# Sheet2.net
KiCad netlist of a schematic drawn in Altium Designer
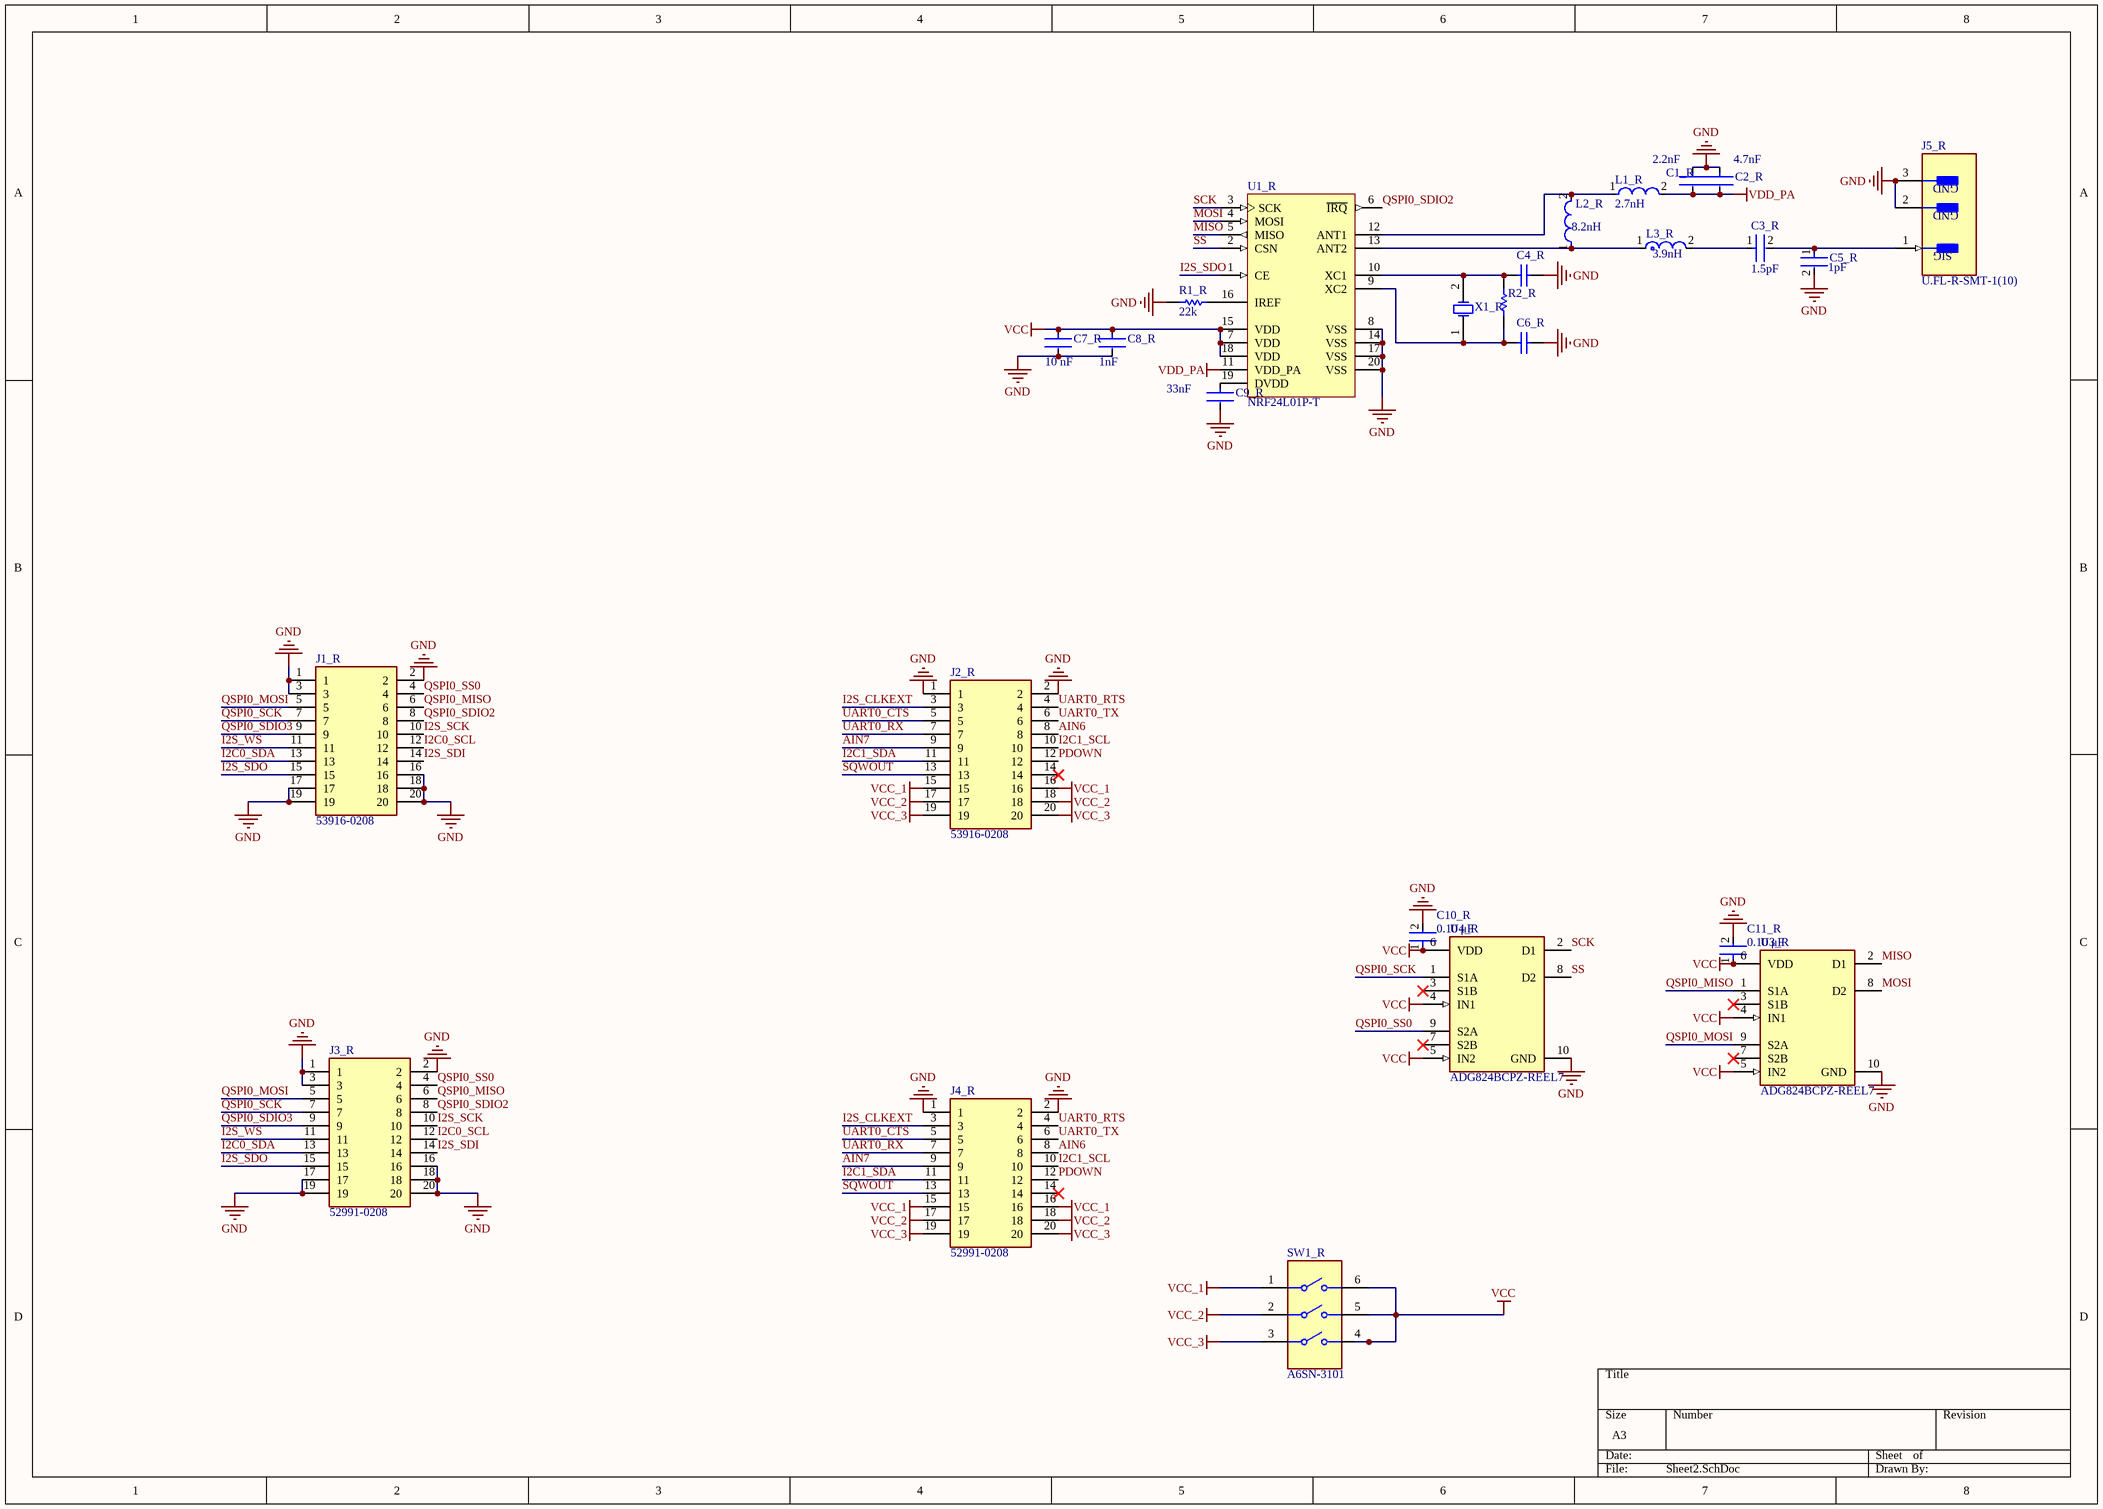
[diagram p0: Sheet2.SchDoc]

(export (version "E")
  (design (tool "Eeschema 10.0.6"))
  (components
    (comp (ref "C1_R")
      (value "GRM155R71H222KA01D")
      (footprint "FP-GRM155-0_05-IPC_B")
      (description "Chip Multilayer Ceramic Capacitors for General Purpose, 0402, 2200pF, X7R, 15%, 10%, 50V")
      (fields
        (field (name "VOLTAGE") "50V")
        (field (name "TOLERANCE") "10%")
        (field (name "CAPACITANCE") "2.2nF")
      )
      (libsource (lib "Altium Content Vault") (part "02cd4be3c70576c341d710602a673aa"))
    )
    (comp (ref "C2_R")
      (value "GRM155R71H472KA01D")
      (footprint "FP-GRM155-0_05-IPC_B")
      (description "Chip Multilayer Ceramic Capacitors for General Purpose, 0402, 4700pF, X7R, 15%, 10%, 50V")
      (fields
        (field (name "VOLTAGE") "50V")
        (field (name "CAPACITANCE") "4.7nF")
        (field (name "TOLERANCE") "10%")
      )
      (libsource (lib "Altium Content Vault") (part "02cd4be3c70576c341d710602a673aa"))
    )
    (comp (ref "C3_R")
      (value "GJM1555C1H1R5BB01D")
      (footprint "FP-GJM155-0_05-IPC_C")
      (description "Multi-Layer Ceramic Capacitor 1.5pF C0G  ±0.1pF 0402 Paper T/R")
      (fields (field (name "CAPACITANCE") "1.5pF") (field (name "VOLTAGE") "50V"))
      (libsource (lib "") (part "02cd4be3c70576c341d710602a673aa_1"))
    )
    (comp (ref "C4_R")
      (value "04025A220JAT2A")
      (footprint "CAPC1005X56X25NL10T15")
      (fields (field (name "MANUFACTURER") "AVX Interconnect / Elco"))
      (libsource (lib "Altium Content Vault") (part "CAP"))
    )
    (comp (ref "C5_R")
      (value "GJM1555C1H1R0BB01D")
      (footprint "FP-GJM155-0_05-IPC_B")
      (description "Multi-Layer Ceramic Capacitor 1pF C0G  ±0.1pF 0402 Paper T/R")
      (fields (field (name "CAPACITANCE") "1pF") (field (name "VOLTAGE") "50V"))
      (libsource (lib "") (part "02cd4be3c70576c341d710602a673aa_1"))
    )
    (comp (ref "C6_R")
      (value "04025A220JAT2A")
      (footprint "CAPC1005X56X25NL10T15")
      (fields (field (name "MANUFACTURER") "AVX Interconnect / Elco"))
      (libsource (lib "Altium Content Vault") (part "CAP"))
    )
    (comp (ref "C7_R")
      (value "CC0402KRX7R7BB103")
      (footprint "FP-CC0402-MFG")
      (description "CAP CER 10000PF 16V X7R 0402")
      (fields
        (field (name "CAPACITANCE") "10 nF")
        (field (name "TOLERANCE") "0.1")
        (field (name "MANUFACTURER") "YAGEO")
      )
      (libsource (lib "Altium Content Vault") (part "11868f565c42a9108669ba33697ecf6"))
    )
    (comp (ref "C8_R")
      (value "GRM1555C1H102JA01D")
      (footprint "FP-GRM155-0_05-IPC_B")
      (description "Chip Multilayer Ceramic Capacitors for General Purpose, 0402, 1000pF, C0G, 30ppm/°C, 5%, 50V")
      (fields
        (field (name "TOLERANCE") "5%")
        (field (name "VOLTAGE") "50V")
        (field (name "CAPACITANCE") "1nF")
      )
      (libsource (lib "Altium Content Vault") (part "02cd4be3c70576c341d710602a673aa"))
    )
    (comp (ref "C9_R")
      (value "C0402C333K4RACTU")
      (footprint "FP-C0402-BB-MFG")
      (description "0402 C 33nF Ceramic Multilayer Capacitor; 16 V; +125degC; X7R Dielectric; +/-10%")
      (fields
        (field (name "MANUFACTURER") "Kemet")
        (field (name "CAPACITANCE") "33nF")
        (field (name "OCTOPART") "https://octopart.com/c0402c333k4ractu-kemet-128815")
      )
      (libsource (lib "") (part "b4654b650e69147ec39a6b967a45e02_1"))
    )
    (comp (ref "C10_R")
      (value "C0402C104K8PACTU")
      (footprint "FP-C0402-BB-MFG")
      (description "CAP CER 0.1UF 10V X5R 0402")
      (fields
        (field (name "CAPACITANCE") "0.10 μF")
        (field (name "MANUFACTURER") "Kemet")
        (field (name "TOLERANCE") "0.1")
      )
      (libsource (lib "Altium Content Vault") (part "b4654b650e69147ec39a6b967a45e02"))
    )
    (comp (ref "C11_R")
      (value "C0402C104K8PACTU")
      (footprint "FP-C0402-BB-MFG")
      (description "CAP CER 0.1UF 10V X5R 0402")
      (fields
        (field (name "CAPACITANCE") "0.10 μF")
        (field (name "MANUFACTURER") "Kemet")
        (field (name "TOLERANCE") "0.1")
      )
      (libsource (lib "Altium Content Vault") (part "b4654b650e69147ec39a6b967a45e02"))
    )
    (comp (ref "J1_R")
      (value "53916-0208")
      (footprint "MOLEX-  539160208")
      (libsource (lib "52991-0208") (part "53916-0208"))
    )
    (comp (ref "J2_R")
      (value "53916-0208")
      (footprint "MOLEX-  539160208")
      (libsource (lib "52991-0208") (part "53916-0208"))
    )
    (comp (ref "J3_R")
      (value "52991-0208")
      (footprint "MOLEX_52991-0208")
      (description "20 Position Connector Receptacle, Center Strip Contacts Surface Mount Gold")
      (fields (field (name "MF") "Molex"))
      (libsource (lib "52991-0208") (part "52991-0208"))
    )
    (comp (ref "J4_R")
      (value "52991-0208")
      (footprint "MOLEX_52991-0208")
      (description "20 Position Connector Receptacle, Center Strip Contacts Surface Mount Gold")
      (fields (field (name "MF") "Molex"))
      (libsource (lib "52991-0208") (part "52991-0208"))
    )
    (comp (ref "J5_R")
      (value "U.FL-R-SMT-1(10)")
      (footprint "FP-U_FL-R-SMT-1_10-MFG")
      (description "CONN U.FL RCPT STR 50 OHM SMD")
      (libsource (lib "Altium Content Vault") (part "7158abf7d987fa84906f6fb0d115710"))
    )
    (comp (ref "L1_R")
      (value "LQW15AN2N7C00D")
      (footprint "FP-LQW15AN_00-W0_6-0_1-MFG")
      (description "Wire Wound RF Inductor 2.7nH ±0.2nH 850mA 0.05Ω 0402 (1005)")
      (fields (field (name "INDUCTANCE") "2.7nH"))
      (libsource (lib "Altium Content Vault") (part "725321dda6339637d4d059423bc1c3c"))
    )
    (comp (ref "L2_R")
      (value "LQW15AN8N2G00D")
      (footprint "FP-LQW15AN_00-W0_6-0_1-MFG")
      (description "Wire Wound RF Inductor 8.2nH ±2% 540mA 0.14Ω 0402 (1005)")
      (fields (field (name "TOLERANCE") "2%") (field (name "INDUCTANCE") "8.2nH"))
      (libsource (lib "Altium Content Vault") (part "725321dda6339637d4d059423bc1c3c"))
    )
    (comp (ref "L3_R")
      (value "LQG15HN3N9S02D")
      (footprint "FP-LQG15HH_02-MFG")
      (description "Multilayer type RF Inductor 3.9nH ±0.3nH 0.13Ω 700mA 0402")
      (fields (field (name "INDUCTANCE") "3.9nH"))
      (libsource (lib "Altium Content Vault") (part "4cc4b267dca4c8e51f7102f422741d8"))
    )
    (comp (ref "R1_R")
      (value "CRCW040222K0FKED")
      (footprint "RESC1005X40X25NL05T05")
      (fields (field (name "MANUFACTURER") "Vishay Dale") (field (name "RESISTANCE") "22k"))
      (libsource (lib "Altium Content Vault") (part "RES"))
    )
    (comp (ref "R2_R")
      (value "ERJ-3EKF1004V")
      (footprint "RESC1608X55X30LL15T15")
      (fields (field (name "MANUFACTURER") "Panasonic"))
      (libsource (lib "Altium Content Vault") (part "RES"))
    )
    (comp (ref "SW1_R")
      (value "A6SN-3101")
      (footprint "FP-A6SN-3101-MFG")
      (description "DIP Switches / SIP Switches 3P Knife-Edge, 2.3mm Slide SMT Flat-Act")
      (fields (field (name "MANUFACTURER") "Omron Electronics Inc-EMC Div"))
      (libsource (lib "Altium Content Vault") (part "c5ed29025a0a80be921a75429a93ff4"))
    )
    (comp (ref "U1_R")
      (value "NRF24L01P-T")
      (footprint "NRSC-QFN-20_L")
      (description "Single Chip Transceiver, 2.4 GHz, 60 mW, 1.9 to 3.6 V, -40 to 85 degC, 20-Pin QFN, RoHS, Tray")
      (fields (field (name "MANUFACTURER") "Nordic Semiconductor"))
      (libsource (lib "Altium Content Vault") (part "NRSC-NRF24L01P-QFN-20"))
    )
    (comp (ref "U3_R")
      (value "ADG824BCPZ-REEL7")
      (footprint "FP-CP-10-10-MFG")
      (description "IC SWITCH DUAL SPDT 10LFCSP")
      (fields
        (field (name "OCTOPART") "https://octopart.com/adg824bcpz-reel7-analog+devices-12410880")
        (field (name "MANUFACTURER") "Analog Devices")
      )
      (libsource (lib "Altium Content Vault") (part "750f7653eda72c1ba3820f182f788e1"))
    )
    (comp (ref "U4_R")
      (value "ADG824BCPZ-REEL7")
      (footprint "FP-CP-10-10-MFG")
      (description "IC SWITCH DUAL SPDT 10LFCSP")
      (fields
        (field (name "OCTOPART") "https://octopart.com/adg824bcpz-reel7-analog+devices-12410880")
        (field (name "MANUFACTURER") "Analog Devices")
      )
      (libsource (lib "Altium Content Vault") (part "750f7653eda72c1ba3820f182f788e1"))
    )
    (comp (ref "X1_R")
      (value "FOXSDLF/160-20")
      (footprint "FOX-FOXSDLF160-20_V")
      (libsource (lib "Altium Content Vault") (part "XTAL_1-2-2"))
    )
  )
  (nets
    (net (code "1") (name "/AIN6") (class "Default")
      (node (ref "J2_R") (pin "8") (pinfunction "8_8") (pintype "passive"))
      (node (ref "J4_R") (pin "8") (pinfunction "8_8") (pintype "passive"))
    )
    (net (code "2") (name "/AIN7") (class "Default")
      (node (ref "J2_R") (pin "9") (pinfunction "9_9") (pintype "passive"))
      (node (ref "J4_R") (pin "9") (pinfunction "9_9") (pintype "passive"))
    )
    (net (code "3") (name "/I2C0_SCL") (class "Default")
      (node (ref "J1_R") (pin "12") (pinfunction "12_12") (pintype "passive"))
      (node (ref "J3_R") (pin "12") (pinfunction "12_12") (pintype "passive"))
    )
    (net (code "4") (name "/I2C0_SDA") (class "Default")
      (node (ref "J1_R") (pin "13") (pinfunction "13_13") (pintype "passive"))
      (node (ref "J3_R") (pin "13") (pinfunction "13_13") (pintype "passive"))
    )
    (net (code "5") (name "/I2C1_SCL") (class "Default")
      (node (ref "J2_R") (pin "10") (pinfunction "10_10") (pintype "passive"))
      (node (ref "J4_R") (pin "10") (pinfunction "10_10") (pintype "passive"))
    )
    (net (code "6") (name "/I2C1_SDA") (class "Default")
      (node (ref "J2_R") (pin "11") (pinfunction "11_11") (pintype "passive"))
      (node (ref "J4_R") (pin "11") (pinfunction "11_11") (pintype "passive"))
    )
    (net (code "7") (name "/I2S_CLKEXT") (class "Default")
      (node (ref "J2_R") (pin "3") (pinfunction "3_3") (pintype "passive"))
      (node (ref "J4_R") (pin "3") (pinfunction "3_3") (pintype "passive"))
    )
    (net (code "8") (name "/I2S_SCK") (class "Default")
      (node (ref "J1_R") (pin "10") (pinfunction "10_10") (pintype "passive"))
      (node (ref "J3_R") (pin "10") (pinfunction "10_10") (pintype "passive"))
    )
    (net (code "9") (name "/I2S_SDI") (class "Default")
      (node (ref "J1_R") (pin "14") (pinfunction "14_14") (pintype "passive"))
      (node (ref "J3_R") (pin "14") (pinfunction "14_14") (pintype "passive"))
    )
    (net (code "10") (name "/I2S_SDO") (class "Default")
      (node (ref "J1_R") (pin "15") (pinfunction "15_15") (pintype "passive"))
      (node (ref "J3_R") (pin "15") (pinfunction "15_15") (pintype "passive"))
      (node (ref "U1_R") (pin "1") (pinfunction "CE_1") (pintype "input"))
    )
    (net (code "11") (name "/I2S_WS") (class "Default")
      (node (ref "J1_R") (pin "11") (pinfunction "11_11") (pintype "passive"))
      (node (ref "J3_R") (pin "11") (pinfunction "11_11") (pintype "passive"))
    )
    (net (code "12") (name "/MISO") (class "Default")
      (node (ref "U1_R") (pin "5") (pinfunction "MISO_5") (pintype "output"))
      (node (ref "U3_R") (pin "2") (pinfunction "D1_2") (pintype "passive"))
    )
    (net (code "13") (name "/MOSI") (class "Default")
      (node (ref "U1_R") (pin "4") (pinfunction "MOSI_4") (pintype "input"))
      (node (ref "U3_R") (pin "8") (pinfunction "D2_8") (pintype "passive"))
    )
    (net (code "14") (name "/PDOWN") (class "Default")
      (node (ref "J2_R") (pin "12") (pinfunction "12_12") (pintype "passive"))
      (node (ref "J4_R") (pin "12") (pinfunction "12_12") (pintype "passive"))
    )
    (net (code "15") (name "/QSPI0_MISO") (class "Default")
      (node (ref "J1_R") (pin "6") (pinfunction "6_6") (pintype "passive"))
      (node (ref "J3_R") (pin "6") (pinfunction "6_6") (pintype "passive"))
      (node (ref "U3_R") (pin "1") (pinfunction "S1A_1") (pintype "passive"))
    )
    (net (code "16") (name "/QSPI0_MOSI") (class "Default")
      (node (ref "J1_R") (pin "5") (pinfunction "5_5") (pintype "passive"))
      (node (ref "J3_R") (pin "5") (pinfunction "5_5") (pintype "passive"))
      (node (ref "U3_R") (pin "9") (pinfunction "S2A_9") (pintype "passive"))
    )
    (net (code "17") (name "/QSPI0_SCK") (class "Default")
      (node (ref "J1_R") (pin "7") (pinfunction "7_7") (pintype "passive"))
      (node (ref "J3_R") (pin "7") (pinfunction "7_7") (pintype "passive"))
      (node (ref "U4_R") (pin "1") (pinfunction "S1A_1") (pintype "passive"))
    )
    (net (code "18") (name "/QSPI0_SDIO2") (class "Default")
      (node (ref "J1_R") (pin "8") (pinfunction "8_8") (pintype "passive"))
      (node (ref "J3_R") (pin "8") (pinfunction "8_8") (pintype "passive"))
      (node (ref "U1_R") (pin "6") (pinfunction "~{IRQ}_6") (pintype "output"))
    )
    (net (code "19") (name "/QSPI0_SDIO3") (class "Default")
      (node (ref "J1_R") (pin "9") (pinfunction "9_9") (pintype "passive"))
      (node (ref "J3_R") (pin "9") (pinfunction "9_9") (pintype "passive"))
    )
    (net (code "20") (name "/QSPI0_SS0") (class "Default")
      (node (ref "J1_R") (pin "4") (pinfunction "4_4") (pintype "passive"))
      (node (ref "J3_R") (pin "4") (pinfunction "4_4") (pintype "passive"))
      (node (ref "U4_R") (pin "9") (pinfunction "S2A_9") (pintype "passive"))
    )
    (net (code "21") (name "/SCK") (class "Default")
      (node (ref "U1_R") (pin "3") (pinfunction "SCK_3") (pintype "input"))
      (node (ref "U4_R") (pin "2") (pinfunction "D1_2") (pintype "passive"))
    )
    (net (code "22") (name "/SQWOUT") (class "Default")
      (node (ref "J2_R") (pin "13") (pinfunction "13_13") (pintype "passive"))
      (node (ref "J4_R") (pin "13") (pinfunction "13_13") (pintype "passive"))
    )
    (net (code "23") (name "/SS") (class "Default")
      (node (ref "U1_R") (pin "2") (pinfunction "CSN_2") (pintype "input"))
      (node (ref "U4_R") (pin "8") (pinfunction "D2_8") (pintype "passive"))
    )
    (net (code "24") (name "/UART0_CTS") (class "Default")
      (node (ref "J2_R") (pin "5") (pinfunction "5_5") (pintype "passive"))
      (node (ref "J4_R") (pin "5") (pinfunction "5_5") (pintype "passive"))
    )
    (net (code "25") (name "/UART0_RTS") (class "Default")
      (node (ref "J2_R") (pin "4") (pinfunction "4_4") (pintype "passive"))
      (node (ref "J4_R") (pin "4") (pinfunction "4_4") (pintype "passive"))
    )
    (net (code "26") (name "/UART0_RX") (class "Default")
      (node (ref "J2_R") (pin "7") (pinfunction "7_7") (pintype "passive"))
      (node (ref "J4_R") (pin "7") (pinfunction "7_7") (pintype "passive"))
    )
    (net (code "27") (name "/UART0_TX") (class "Default")
      (node (ref "J2_R") (pin "6") (pinfunction "6_6") (pintype "passive"))
      (node (ref "J4_R") (pin "6") (pinfunction "6_6") (pintype "passive"))
    )
    (net (code "28") (name "GND") (class "Default")
      (node (ref "C10_R") (pin "2") (pinfunction "2_2") (pintype "passive"))
      (node (ref "C11_R") (pin "2") (pinfunction "2_2") (pintype "passive"))
      (node (ref "C1_R") (pin "1") (pinfunction "1_1") (pintype "passive"))
      (node (ref "C2_R") (pin "1") (pinfunction "1_1") (pintype "passive"))
      (node (ref "C4_R") (pin "2") (pinfunction "2_2") (pintype "passive"))
      (node (ref "C5_R") (pin "2") (pinfunction "2_2") (pintype "passive"))
      (node (ref "C6_R") (pin "2") (pinfunction "2_2") (pintype "passive"))
      (node (ref "C7_R") (pin "2") (pinfunction "2_2") (pintype "passive"))
      (node (ref "C8_R") (pin "2") (pinfunction "2_2") (pintype "passive"))
      (node (ref "C9_R") (pin "2") (pinfunction "2_2") (pintype "passive"))
      (node (ref "J1_R") (pin "1") (pinfunction "1_1") (pintype "passive"))
      (node (ref "J1_R") (pin "16") (pinfunction "16_16") (pintype "passive"))
      (node (ref "J1_R") (pin "17") (pinfunction "17_17") (pintype "passive"))
      (node (ref "J1_R") (pin "18") (pinfunction "18_18") (pintype "passive"))
      (node (ref "J1_R") (pin "19") (pinfunction "19_19") (pintype "passive"))
      (node (ref "J1_R") (pin "2") (pinfunction "2_2") (pintype "passive"))
      (node (ref "J1_R") (pin "20") (pinfunction "20_20") (pintype "passive"))
      (node (ref "J1_R") (pin "3") (pinfunction "3_3") (pintype "passive"))
      (node (ref "J2_R") (pin "1") (pinfunction "1_1") (pintype "passive"))
      (node (ref "J2_R") (pin "2") (pinfunction "2_2") (pintype "passive"))
      (node (ref "J3_R") (pin "1") (pinfunction "1_1") (pintype "passive"))
      (node (ref "J3_R") (pin "16") (pinfunction "16_16") (pintype "passive"))
      (node (ref "J3_R") (pin "17") (pinfunction "17_17") (pintype "passive"))
      (node (ref "J3_R") (pin "18") (pinfunction "18_18") (pintype "passive"))
      (node (ref "J3_R") (pin "19") (pinfunction "19_19") (pintype "passive"))
      (node (ref "J3_R") (pin "2") (pinfunction "2_2") (pintype "passive"))
      (node (ref "J3_R") (pin "20") (pinfunction "20_20") (pintype "passive"))
      (node (ref "J3_R") (pin "3") (pinfunction "3_3") (pintype "passive"))
      (node (ref "J4_R") (pin "1") (pinfunction "1_1") (pintype "passive"))
      (node (ref "J4_R") (pin "2") (pinfunction "2_2") (pintype "passive"))
      (node (ref "J5_R") (pin "2") (pinfunction "GND_2") (pintype "power_in"))
      (node (ref "J5_R") (pin "3") (pinfunction "GND_3") (pintype "power_in"))
      (node (ref "R1_R") (pin "1") (pinfunction "1_1") (pintype "passive"))
      (node (ref "U1_R") (pin "14") (pinfunction "VSS_14") (pintype "power_in"))
      (node (ref "U1_R") (pin "17") (pinfunction "VSS_17") (pintype "power_in"))
      (node (ref "U1_R") (pin "20") (pinfunction "VSS_20") (pintype "power_in"))
      (node (ref "U1_R") (pin "8") (pinfunction "VSS_8") (pintype "power_in"))
      (node (ref "U3_R") (pin "10") (pinfunction "GND_10") (pintype "power_in"))
      (node (ref "U4_R") (pin "10") (pinfunction "GND_10") (pintype "power_in"))
    )
    (net (code "29") (name "Net-(C3_R-Pad1)") (class "Default")
      (node (ref "C3_R") (pin "1") (pinfunction "1_1") (pintype "passive"))
      (node (ref "L3_R") (pin "2") (pinfunction "2_2") (pintype "passive"))
    )
    (net (code "30") (name "Net-(J5_R-SIG)") (class "Default")
      (node (ref "C3_R") (pin "2") (pinfunction "2_2") (pintype "passive"))
      (node (ref "C5_R") (pin "1") (pinfunction "1_1") (pintype "passive"))
      (node (ref "J5_R") (pin "1") (pinfunction "SIG_1") (pintype "input"))
    )
    (net (code "31") (name "Net-(U1_R-ANT1)") (class "Default")
      (node (ref "L1_R") (pin "1") (pinfunction "1_1") (pintype "passive"))
      (node (ref "L2_R") (pin "2") (pinfunction "2_2") (pintype "passive"))
      (node (ref "U1_R") (pin "12") (pinfunction "ANT1_12") (pintype "passive"))
    )
    (net (code "32") (name "Net-(U1_R-ANT2)") (class "Default")
      (node (ref "L2_R") (pin "1") (pinfunction "1_1") (pintype "passive"))
      (node (ref "L3_R") (pin "1") (pinfunction "1_1") (pintype "passive"))
      (node (ref "U1_R") (pin "13") (pinfunction "ANT2_13") (pintype "passive"))
    )
    (net (code "33") (name "Net-(U1_R-DVDD)") (class "Default")
      (node (ref "C9_R") (pin "1") (pinfunction "1_1") (pintype "passive"))
      (node (ref "U1_R") (pin "19") (pinfunction "DVDD_19") (pintype "power_in"))
    )
    (net (code "34") (name "Net-(U1_R-IREF)") (class "Default")
      (node (ref "R1_R") (pin "2") (pinfunction "2_2") (pintype "passive"))
      (node (ref "U1_R") (pin "16") (pinfunction "IREF_16") (pintype "passive"))
    )
    (net (code "35") (name "Net-(U1_R-XC1)") (class "Default")
      (node (ref "C4_R") (pin "1") (pinfunction "1_1") (pintype "passive"))
      (node (ref "R2_R") (pin "2") (pinfunction "2_2") (pintype "passive"))
      (node (ref "U1_R") (pin "10") (pinfunction "XC1_10") (pintype "passive"))
      (node (ref "X1_R") (pin "2") (pinfunction "X2_2") (pintype "passive"))
    )
    (net (code "36") (name "Net-(U1_R-XC2)") (class "Default")
      (node (ref "C6_R") (pin "1") (pinfunction "1_1") (pintype "passive"))
      (node (ref "R2_R") (pin "1") (pinfunction "1_1") (pintype "passive"))
      (node (ref "U1_R") (pin "9") (pinfunction "XC2_9") (pintype "passive"))
      (node (ref "X1_R") (pin "1") (pinfunction "X1_1") (pintype "passive"))
    )
    (net (code "37") (name "VCC") (class "Default")
      (node (ref "C10_R") (pin "1") (pinfunction "1_1") (pintype "passive"))
      (node (ref "C11_R") (pin "1") (pinfunction "1_1") (pintype "passive"))
      (node (ref "C7_R") (pin "1") (pinfunction "1_1") (pintype "passive"))
      (node (ref "C8_R") (pin "1") (pinfunction "1_1") (pintype "passive"))
      (node (ref "SW1_R") (pin "4") (pinfunction "4_4") (pintype "passive"))
      (node (ref "SW1_R") (pin "5") (pinfunction "5_5") (pintype "passive"))
      (node (ref "SW1_R") (pin "6") (pinfunction "6_6") (pintype "passive"))
      (node (ref "U1_R") (pin "15") (pinfunction "VDD_15") (pintype "power_in"))
      (node (ref "U1_R") (pin "18") (pinfunction "VDD_18") (pintype "power_in"))
      (node (ref "U1_R") (pin "7") (pinfunction "VDD_7") (pintype "power_in"))
      (node (ref "U3_R") (pin "4") (pinfunction "IN1_4") (pintype "input"))
      (node (ref "U3_R") (pin "5") (pinfunction "IN2_5") (pintype "input"))
      (node (ref "U3_R") (pin "6") (pinfunction "VDD_6") (pintype "power_in"))
      (node (ref "U4_R") (pin "4") (pinfunction "IN1_4") (pintype "input"))
      (node (ref "U4_R") (pin "5") (pinfunction "IN2_5") (pintype "input"))
      (node (ref "U4_R") (pin "6") (pinfunction "VDD_6") (pintype "power_in"))
    )
    (net (code "38") (name "VCC_1") (class "Default")
      (node (ref "J2_R") (pin "15") (pinfunction "15_15") (pintype "passive"))
      (node (ref "J2_R") (pin "16") (pinfunction "16_16") (pintype "passive"))
      (node (ref "J4_R") (pin "15") (pinfunction "15_15") (pintype "passive"))
      (node (ref "J4_R") (pin "16") (pinfunction "16_16") (pintype "passive"))
      (node (ref "SW1_R") (pin "1") (pinfunction "1_1") (pintype "passive"))
    )
    (net (code "39") (name "VCC_2") (class "Default")
      (node (ref "J2_R") (pin "17") (pinfunction "17_17") (pintype "passive"))
      (node (ref "J2_R") (pin "18") (pinfunction "18_18") (pintype "passive"))
      (node (ref "J4_R") (pin "17") (pinfunction "17_17") (pintype "passive"))
      (node (ref "J4_R") (pin "18") (pinfunction "18_18") (pintype "passive"))
      (node (ref "SW1_R") (pin "2") (pinfunction "2_2") (pintype "passive"))
    )
    (net (code "40") (name "VCC_3") (class "Default")
      (node (ref "J2_R") (pin "19") (pinfunction "19_19") (pintype "passive"))
      (node (ref "J2_R") (pin "20") (pinfunction "20_20") (pintype "passive"))
      (node (ref "J4_R") (pin "19") (pinfunction "19_19") (pintype "passive"))
      (node (ref "J4_R") (pin "20") (pinfunction "20_20") (pintype "passive"))
      (node (ref "SW1_R") (pin "3") (pinfunction "3_3") (pintype "passive"))
    )
    (net (code "41") (name "VDD_PA") (class "Default")
      (node (ref "C1_R") (pin "2") (pinfunction "2_2") (pintype "passive"))
      (node (ref "C2_R") (pin "2") (pinfunction "2_2") (pintype "passive"))
      (node (ref "L1_R") (pin "2") (pinfunction "2_2") (pintype "passive"))
      (node (ref "U1_R") (pin "11") (pinfunction "VDD_PA_11") (pintype "power_in"))
    )
    (net (code "42") (name "unconnected-(J2_R-Pad14)") (class "Default")
      (node (ref "J2_R") (pin "14") (pinfunction "14_14") (pintype "passive+no_connect"))
    )
    (net (code "43") (name "unconnected-(J4_R-Pad14)") (class "Default")
      (node (ref "J4_R") (pin "14") (pinfunction "14_14") (pintype "passive+no_connect"))
    )
    (net (code "44") (name "unconnected-(U3_R-S1B-Pad3)") (class "Default")
      (node (ref "U3_R") (pin "3") (pinfunction "S1B_3") (pintype "passive+no_connect"))
    )
    (net (code "45") (name "unconnected-(U3_R-S2B-Pad7)") (class "Default")
      (node (ref "U3_R") (pin "7") (pinfunction "S2B_7") (pintype "passive+no_connect"))
    )
    (net (code "46") (name "unconnected-(U4_R-S1B-Pad3)") (class "Default")
      (node (ref "U4_R") (pin "3") (pinfunction "S1B_3") (pintype "passive+no_connect"))
    )
    (net (code "47") (name "unconnected-(U4_R-S2B-Pad7)") (class "Default")
      (node (ref "U4_R") (pin "7") (pinfunction "S2B_7") (pintype "passive+no_connect"))
    )
  )
)
